# FM349ReaderV02.net
KiCad netlist of a schematic drawn in Altium Designer
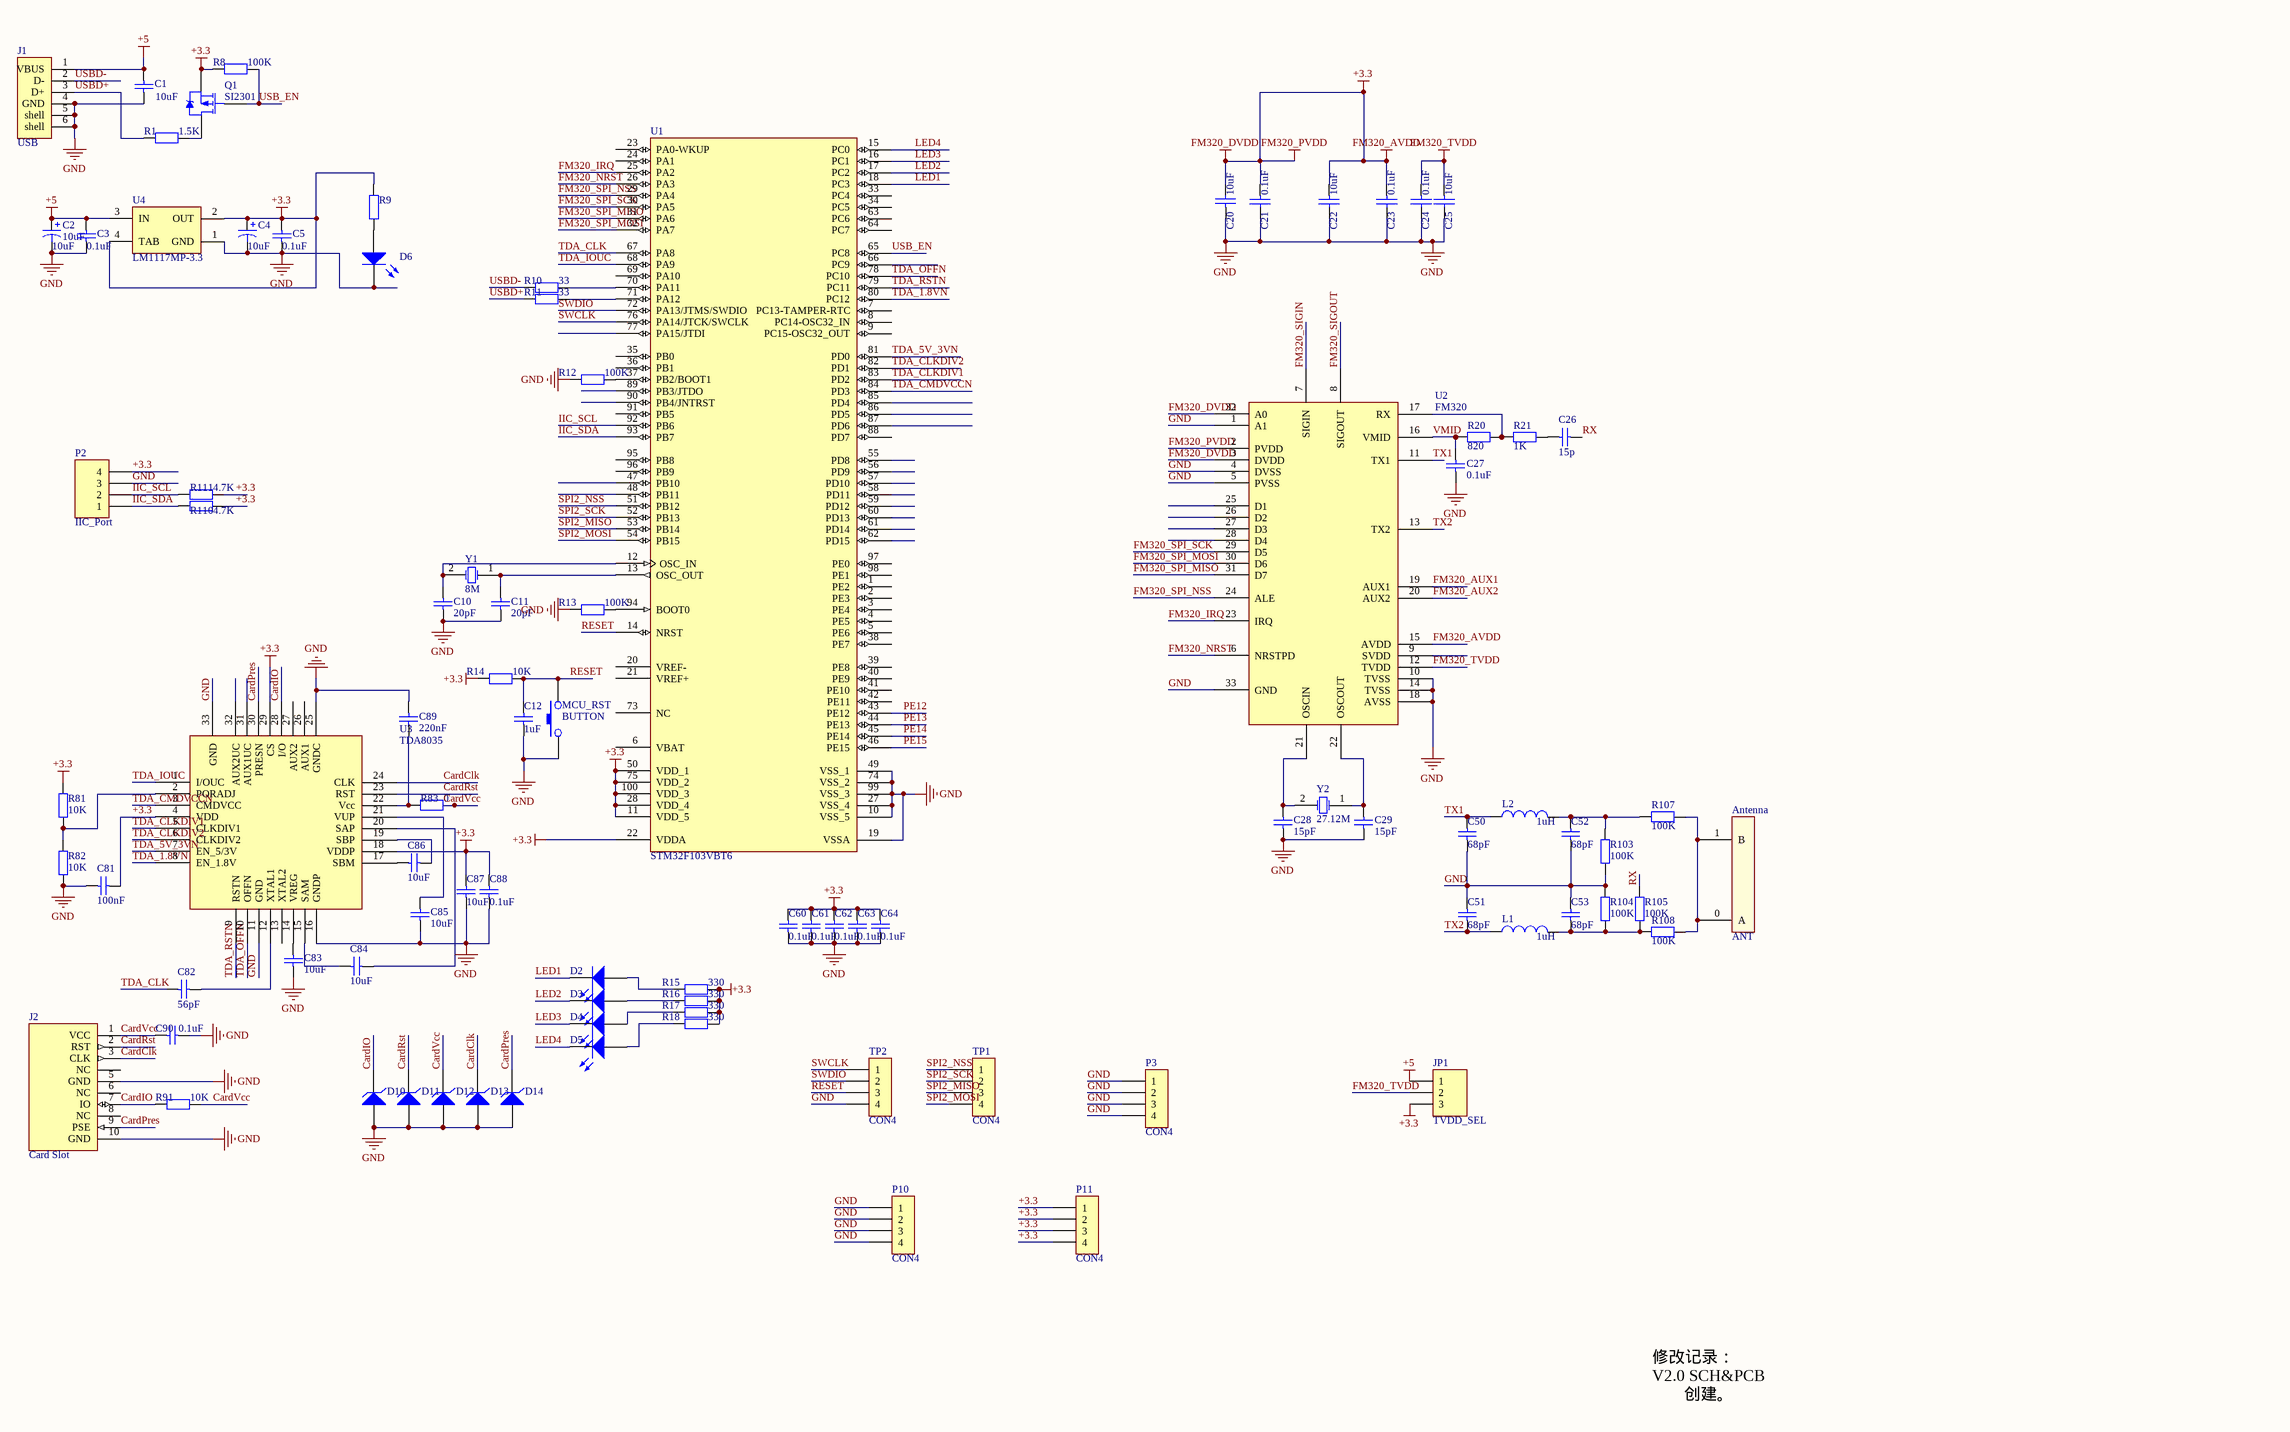
[diagram p0: FM349ReaderV02.SchDoc]

(export (version "E")
  (design (tool "Eeschema 10.0.6"))
  (components
    (comp (ref "Antenna") (value "ANT") (footprint "Antenna") (libsource (lib "FM349ReaderV01") (part "ANT")))
    (comp (ref "C1")
      (value "10uF")
      (footprint "0603")
      (description "Capacitor")
      (libsource (lib "Miscellaneous Devices") (part "Cap"))
    )
    (comp (ref "C2")
      (value "10uF")
      (footprint "0805")
      (description "Polarized Capacitor (Radial)")
      (fields (field (name "ALTIUM_VALUE") "10uF"))
      (libsource (lib "Miscellaneous Devices") (part "Cap Pol1"))
    )
    (comp (ref "C3")
      (value "0.1uF")
      (footprint "0603")
      (description "Capacitor")
      (libsource (lib "Miscellaneous Devices") (part "Cap"))
    )
    (comp (ref "C4")
      (value "10uF")
      (footprint "0805")
      (description "Polarized Capacitor (Radial)")
      (libsource (lib "Miscellaneous Devices") (part "Cap Pol1"))
    )
    (comp (ref "C5")
      (value "0.1uF")
      (footprint "0603")
      (description "Capacitor")
      (libsource (lib "Miscellaneous Devices") (part "Cap"))
    )
    (comp (ref "C10")
      (value "20pF")
      (footprint "0603")
      (description "Capacitor")
      (libsource (lib "Miscellaneous Devices") (part "Cap"))
    )
    (comp (ref "C11")
      (value "20pF")
      (footprint "0603")
      (description "Capacitor")
      (libsource (lib "Miscellaneous Devices") (part "Cap"))
    )
    (comp (ref "C12")
      (value "1uF")
      (footprint "0603")
      (description "Capacitor")
      (libsource (lib "Miscellaneous Devices") (part "Cap"))
    )
    (comp (ref "C20")
      (value "10uF")
      (footprint "0603")
      (description "Capacitor")
      (libsource (lib "SCH_LIB") (part "CAP"))
    )
    (comp (ref "C21")
      (value "0.1uF")
      (footprint "0603")
      (description "Capacitor")
      (libsource (lib "SCH_LIB") (part "CAP"))
    )
    (comp (ref "C22")
      (value "10uF")
      (footprint "0603")
      (description "Capacitor")
      (libsource (lib "SCH_LIB") (part "CAP"))
    )
    (comp (ref "C23")
      (value "0.1uF")
      (footprint "0603")
      (description "Capacitor")
      (libsource (lib "SCH_LIB") (part "CAP"))
    )
    (comp (ref "C24")
      (value "0.1uF")
      (footprint "0603")
      (description "Capacitor")
      (libsource (lib "SCH_LIB") (part "CAP"))
    )
    (comp (ref "C25")
      (value "10uF")
      (footprint "0603")
      (description "Capacitor")
      (libsource (lib "SCH_LIB") (part "CAP"))
    )
    (comp (ref "C26")
      (value "15p")
      (footprint "0603")
      (description "Capacitor")
      (fields (field (name "Comment") "0.1uF"))
      (libsource (lib "Miscellaneous Devices") (part "Cap"))
    )
    (comp (ref "C27")
      (value "0.1uF")
      (footprint "0603")
      (description "Capacitor")
      (libsource (lib "Miscellaneous Devices") (part "Cap"))
    )
    (comp (ref "C28")
      (value "15pF")
      (footprint "0603")
      (description "Capacitor")
      (libsource (lib "Miscellaneous Devices") (part "Cap"))
    )
    (comp (ref "C29")
      (value "15pF")
      (footprint "0603")
      (description "Capacitor")
      (libsource (lib "Miscellaneous Devices") (part "Cap"))
    )
    (comp (ref "C50")
      (value "68pF")
      (footprint "0603")
      (description "Capacitor")
      (libsource (lib "Miscellaneous Devices") (part "Cap"))
    )
    (comp (ref "C51")
      (value "68pF")
      (footprint "0603")
      (description "Capacitor")
      (libsource (lib "Miscellaneous Devices") (part "Cap"))
    )
    (comp (ref "C52")
      (value "68pF")
      (footprint "0603")
      (description "Capacitor")
      (libsource (lib "Miscellaneous Devices") (part "Cap"))
    )
    (comp (ref "C53")
      (value "68pF")
      (footprint "0603")
      (description "Capacitor")
      (libsource (lib "Miscellaneous Devices") (part "Cap"))
    )
    (comp (ref "C60")
      (value "0.1uF")
      (footprint "0603")
      (description "Capacitor")
      (libsource (lib "Miscellaneous Devices") (part "Cap"))
    )
    (comp (ref "C61")
      (value "0.1uF")
      (footprint "0603")
      (description "Capacitor")
      (libsource (lib "Miscellaneous Devices") (part "Cap"))
    )
    (comp (ref "C62")
      (value "0.1uF")
      (footprint "0603")
      (description "Capacitor")
      (libsource (lib "Miscellaneous Devices") (part "Cap"))
    )
    (comp (ref "C63")
      (value "0.1uF")
      (footprint "0603")
      (description "Capacitor")
      (libsource (lib "Miscellaneous Devices") (part "Cap"))
    )
    (comp (ref "C64")
      (value "0.1uF")
      (footprint "0603")
      (description "Capacitor")
      (libsource (lib "Miscellaneous Devices") (part "Cap"))
    )
    (comp (ref "C81")
      (value "100nF")
      (footprint "0603")
      (description "Capacitor")
      (fields (field (name "Comment") "0.1uF"))
      (libsource (lib "Miscellaneous Devices") (part "Cap"))
    )
    (comp (ref "C82")
      (value "56pF")
      (footprint "0603")
      (description "Capacitor")
      (fields (field (name "Comment") "0.1uF"))
      (libsource (lib "Miscellaneous Devices") (part "Cap"))
    )
    (comp (ref "C83")
      (value "10uF")
      (footprint "0603")
      (description "Capacitor")
      (fields (field (name "Comment") "0.1uF"))
      (libsource (lib "Miscellaneous Devices") (part "Cap"))
    )
    (comp (ref "C84")
      (value "10uF")
      (footprint "0603")
      (description "Capacitor")
      (fields (field (name "Comment") "0.1uF"))
      (libsource (lib "Miscellaneous Devices") (part "Cap"))
    )
    (comp (ref "C85")
      (value "10uF")
      (footprint "0603")
      (description "Capacitor")
      (fields (field (name "Comment") "0.1uF"))
      (libsource (lib "Miscellaneous Devices") (part "Cap"))
    )
    (comp (ref "C86")
      (value "10uF")
      (footprint "0603")
      (description "Capacitor")
      (fields (field (name "Comment") "0.1uF"))
      (libsource (lib "Miscellaneous Devices") (part "Cap"))
    )
    (comp (ref "C87")
      (value "10uF")
      (footprint "0603")
      (description "Capacitor")
      (fields (field (name "Comment") "0.1uF"))
      (libsource (lib "Miscellaneous Devices") (part "Cap"))
    )
    (comp (ref "C88")
      (value "0.1uF")
      (footprint "0603")
      (description "Capacitor")
      (libsource (lib "Miscellaneous Devices") (part "Cap"))
    )
    (comp (ref "C89")
      (value "220nF")
      (footprint "0603")
      (description "Capacitor")
      (fields (field (name "Comment") "0.1uF"))
      (libsource (lib "Miscellaneous Devices") (part "Cap"))
    )
    (comp (ref "C90")
      (value "0.1uF")
      (footprint "0603")
      (description "Capacitor")
      (libsource (lib "Miscellaneous Devices") (part "Cap"))
    )
    (comp (ref "D2")
      (value "LED2")
      (footprint "3.2X1.6X1.1")
      (description "Typical RED, GREEN, YELLOW, AMBER GaAs LED")
      (libsource (lib "Miscellaneous Devices") (part "LED2"))
    )
    (comp (ref "D3")
      (value "LED2")
      (footprint "3.2X1.6X1.1")
      (description "Typical RED, GREEN, YELLOW, AMBER GaAs LED")
      (libsource (lib "Miscellaneous Devices") (part "LED2"))
    )
    (comp (ref "D4")
      (value "LED2")
      (footprint "3.2X1.6X1.1")
      (description "Typical RED, GREEN, YELLOW, AMBER GaAs LED")
      (libsource (lib "Miscellaneous Devices") (part "LED2"))
    )
    (comp (ref "D5")
      (value "LED2")
      (footprint "3.2X1.6X1.1")
      (description "Typical RED, GREEN, YELLOW, AMBER GaAs LED")
      (libsource (lib "Miscellaneous Devices") (part "LED2"))
    )
    (comp (ref "D6")
      (value "LED2")
      (footprint "3.2X1.6X1.1")
      (description "Typical RED, GREEN, YELLOW, AMBER GaAs LED")
      (libsource (lib "Miscellaneous Devices") (part "LED2"))
    )
    (comp (ref "D10")
      (value "ESD")
      (footprint "SOD-323")
      (description "Zener Diode")
      (libsource (lib "Miscellaneous Devices") (part "D Zener"))
    )
    (comp (ref "D11")
      (value "ESD")
      (footprint "SOD-323")
      (description "Zener Diode")
      (libsource (lib "Miscellaneous Devices") (part "D Zener"))
    )
    (comp (ref "D12")
      (value "ESD")
      (footprint "SOD-323")
      (description "Zener Diode")
      (libsource (lib "Miscellaneous Devices") (part "D Zener"))
    )
    (comp (ref "D13")
      (value "ESD")
      (footprint "SOD-323")
      (description "Zener Diode")
      (libsource (lib "Miscellaneous Devices") (part "D Zener"))
    )
    (comp (ref "D14")
      (value "ESD")
      (footprint "SOD-323")
      (description "Zener Diode")
      (libsource (lib "Miscellaneous Devices") (part "D Zener"))
    )
    (comp (ref "J1") (value "USB") (footprint "USB-B") (libsource (lib "USB") (part "USB")))
    (comp (ref "J2")
      (value "Card Slot")
      (footprint "BIG-CARD-SLOT")
      (libsource (lib "fm274") (part "Card Slot"))
    )
    (comp (ref "JP1")
      (value "TVDD_SEL")
      (footprint "HDR1X3")
      (description "Header, 3-Pin")
      (libsource (lib "Miscellaneous Connectors") (part "Header 3"))
    )
    (comp (ref "L1")
      (value "1uH")
      (footprint "1812")
      (description "Inductor")
      (libsource (lib "Miscellaneous Devices") (part "Inductor"))
    )
    (comp (ref "L2")
      (value "1uH")
      (footprint "1812")
      (description "Inductor")
      (libsource (lib "Miscellaneous Devices") (part "Inductor"))
    )
    (comp (ref "MCU_RST")
      (value "BUTTON")
      (footprint "BUTTON-S")
      (description "乒乓球按键（压下后接通，松开自动断开），较大按键尺寸12mmX12mm选用BUTTON-L封装，较小尺寸6mmX6mm选用BUTTON-S封装")
      (libsource (lib "fm274") (part "BUTTON"))
    )
    (comp (ref "P2")
      (value "IIC_Port")
      (footprint "HDR1X4")
      (description "Header, 4-Pin")
      (libsource (lib "Miscellaneous Connectors") (part "Header 4"))
    )
    (comp (ref "P3")
      (value "CON4")
      (footprint "HDR1X4")
      (description "Connector")
      (libsource (lib "YPF") (part "CON4"))
    )
    (comp (ref "P10")
      (value "CON4")
      (footprint "HDR1X4")
      (description "Connector")
      (libsource (lib "YPF") (part "CON4"))
    )
    (comp (ref "P11")
      (value "CON4")
      (footprint "HDR1X4")
      (description "Connector")
      (libsource (lib "YPF") (part "CON4"))
    )
    (comp (ref "Q1")
      (value "SI2301")
      (footprint "SOT-23-2301")
      (description "P-Channel Power MOSFET")
      (libsource (lib "Miscellaneous Devices") (part "PMOS-2"))
    )
    (comp (ref "R1")
      (value "1.5K")
      (footprint "0603")
      (description "Resistor")
      (libsource (lib "") (part "Res2_1"))
    )
    (comp (ref "R8")
      (value "100K")
      (footprint "0603")
      (description "Resistor")
      (fields (field (name "Comment") "10K"))
      (libsource (lib "") (part "Res2_1"))
    )
    (comp (ref "R9")
      (value "1.5K")
      (footprint "0603")
      (description "Resistor")
      (libsource (lib "Miscellaneous Devices") (part "Res2"))
    )
    (comp (ref "R10")
      (value "33")
      (footprint "0603")
      (description "Resistor")
      (libsource (lib "") (part "Res2_1"))
    )
    (comp (ref "R11")
      (value "33")
      (footprint "0603")
      (description "Resistor")
      (libsource (lib "") (part "Res2_1"))
    )
    (comp (ref "R12")
      (value "100K")
      (footprint "0603")
      (description "Resistor")
      (libsource (lib "") (part "Res2_1"))
    )
    (comp (ref "R13")
      (value "100K")
      (footprint "0603")
      (description "Resistor")
      (libsource (lib "") (part "Res2_1"))
    )
    (comp (ref "R14")
      (value "10K")
      (footprint "0603")
      (description "Resistor")
      (libsource (lib "") (part "Res2_1"))
    )
    (comp (ref "R15")
      (value "330")
      (footprint "0603")
      (description "Resistor")
      (libsource (lib "") (part "Res2_1"))
    )
    (comp (ref "R16")
      (value "330")
      (footprint "0603")
      (description "Resistor")
      (libsource (lib "") (part "Res2_2"))
    )
    (comp (ref "R17")
      (value "330")
      (footprint "0603")
      (description "Resistor")
      (libsource (lib "") (part "Res2_1"))
    )
    (comp (ref "R18")
      (value "330")
      (footprint "0603")
      (description "Resistor")
      (libsource (lib "") (part "Res2_1"))
    )
    (comp (ref "R20")
      (value "820")
      (footprint "0603")
      (description "Resistor")
      (libsource (lib "") (part "Res2_2"))
    )
    (comp (ref "R21")
      (value "1K")
      (footprint "0603")
      (description "Resistor")
      (libsource (lib "") (part "Res2_2"))
    )
    (comp (ref "R81")
      (value "10K")
      (footprint "0603")
      (description "Resistor")
      (fields (field (name "Comment") "1.5K"))
      (libsource (lib "Miscellaneous Devices") (part "Res2"))
    )
    (comp (ref "R82")
      (value "10K")
      (footprint "0603")
      (description "Resistor")
      (fields (field (name "Comment") "1.5K"))
      (libsource (lib "Miscellaneous Devices") (part "Res2"))
    )
    (comp (ref "R83")
      (value "0")
      (footprint "0603")
      (description "Resistor")
      (fields (field (name "Comment") "10K"))
      (libsource (lib "") (part "Res2_1"))
    )
    (comp (ref "R91")
      (value "10K")
      (footprint "0603")
      (description "Resistor")
      (fields (field (name "Comment") "1.5K"))
      (libsource (lib "") (part "Res2_1"))
    )
    (comp (ref "R103")
      (value "100K")
      (footprint "0603")
      (description "Resistor")
      (libsource (lib "Miscellaneous Devices") (part "Res2"))
    )
    (comp (ref "R104")
      (value "100K")
      (footprint "0603")
      (description "Resistor")
      (libsource (lib "Miscellaneous Devices") (part "Res2"))
    )
    (comp (ref "R105")
      (value "100K")
      (footprint "0603")
      (description "Resistor")
      (libsource (lib "Miscellaneous Devices") (part "Res2"))
    )
    (comp (ref "R107")
      (value "100K")
      (footprint "0603")
      (description "Resistor")
      (libsource (lib "") (part "Res2_2"))
    )
    (comp (ref "R108")
      (value "100K")
      (footprint "0603")
      (description "Resistor")
      (libsource (lib "") (part "Res2_2"))
    )
    (comp (ref "R110")
      (value "4.7K")
      (footprint "0603")
      (description "Resistor")
      (fields (field (name "Comment") "1.5K"))
      (libsource (lib "") (part "Res2_2"))
    )
    (comp (ref "R111")
      (value "4.7K")
      (footprint "0603")
      (description "Resistor")
      (fields (field (name "Comment") "1.5K"))
      (libsource (lib "") (part "Res2_2"))
    )
    (comp (ref "TP1")
      (value "CON4")
      (footprint "HDR1X4")
      (description "Connector")
      (libsource (lib "YPF") (part "CON4"))
    )
    (comp (ref "TP2")
      (value "CON4")
      (footprint "HDR1X4")
      (description "Connector")
      (libsource (lib "YPF") (part "CON4"))
    )
    (comp (ref "U1")
      (value "STM32F103VBT6")
      (footprint "LQFP100_L")
      (description "STM32 ARM-based 32-bit MCU with 64 Kbytes Flash, 100-pin LQFP, Industrial Temperature")
      (libsource (lib "ST Microcontroller 32-Bit STM32") (part "STM32F103VBT6"))
    )
    (comp (ref "U2")
      (value "FM320")
      (footprint "FM320_PIN32")
      (libsource (lib "FM349ReaderV01") (part "PN5120A0HN1"))
    )
    (comp (ref "U3")
      (value "TDA8035")
      (footprint "TDA8035_PIN32")
      (libsource (lib "FM349ReaderV01") (part "TDA8035"))
    )
    (comp (ref "U4")
      (value "LM1117MP-3.3")
      (footprint "MP04A_L")
      (description "800mA Low-Dropout Linear Regulator")
      (fields
        (field (name "MANUFACTURER") "National Semiconductor")
        (field (name "DIGIKEYPARTNUMBER") "LM1117MP-3.3CT-ND")
      )
      (libsource (lib "NSC LDO") (part "LM1117MP-3.3"))
    )
    (comp (ref "Y1")
      (value "8M")
      (footprint "XTAL-0.2")
      (description "Crystal Oscillator")
      (libsource (lib "Miscellaneous Devices") (part "XTAL"))
    )
    (comp (ref "Y2")
      (value "27.12M")
      (footprint "XTAL-0.2")
      (description "Crystal Oscillator")
      (libsource (lib "Miscellaneous Devices") (part "XTAL"))
    )
  )
  (nets
    (net (code "1") (name "+3.3") (class "Default")
      (node (ref "C20") (pin "2") (pinfunction "2_2") (pintype "passive"))
      (node (ref "C21") (pin "1") (pinfunction "1_1") (pintype "passive"))
      (node (ref "C22") (pin "1") (pinfunction "1_1") (pintype "passive"))
      (node (ref "C23") (pin "1") (pinfunction "1_1") (pintype "passive"))
      (node (ref "C4") (pin "1") (pinfunction "1_1") (pintype "passive"))
      (node (ref "C5") (pin "2") (pinfunction "2_2") (pintype "passive"))
      (node (ref "C60") (pin "2") (pinfunction "2_2") (pintype "passive"))
      (node (ref "C61") (pin "2") (pinfunction "2_2") (pintype "passive"))
      (node (ref "C62") (pin "2") (pinfunction "2_2") (pintype "passive"))
      (node (ref "C63") (pin "2") (pinfunction "2_2") (pintype "passive"))
      (node (ref "C64") (pin "2") (pinfunction "2_2") (pintype "passive"))
      (node (ref "C81") (pin "1") (pinfunction "1_1") (pintype "passive"))
      (node (ref "C87") (pin "2") (pinfunction "2_2") (pintype "passive"))
      (node (ref "C88") (pin "2") (pinfunction "2_2") (pintype "passive"))
      (node (ref "JP1") (pin "3") (pinfunction "3_3") (pintype "passive"))
      (node (ref "P11") (pin "1") (pinfunction "1_1") (pintype "passive"))
      (node (ref "P11") (pin "2") (pinfunction "2_2") (pintype "passive"))
      (node (ref "P11") (pin "3") (pinfunction "3_3") (pintype "passive"))
      (node (ref "P11") (pin "4") (pinfunction "4_4") (pintype "passive"))
      (node (ref "P2") (pin "4") (pinfunction "4_4") (pintype "passive"))
      (node (ref "Q1") (pin "3") (pinfunction "S_3") (pintype "passive"))
      (node (ref "R110") (pin "1") (pinfunction "1_1") (pintype "passive"))
      (node (ref "R111") (pin "1") (pinfunction "1_1") (pintype "passive"))
      (node (ref "R14") (pin "1") (pinfunction "1_1") (pintype "passive"))
      (node (ref "R15") (pin "2") (pinfunction "2_2") (pintype "passive"))
      (node (ref "R16") (pin "1") (pinfunction "1_1") (pintype "passive"))
      (node (ref "R17") (pin "2") (pinfunction "2_2") (pintype "passive"))
      (node (ref "R18") (pin "2") (pinfunction "2_2") (pintype "passive"))
      (node (ref "R8") (pin "1") (pinfunction "1_1") (pintype "passive"))
      (node (ref "R81") (pin "2") (pinfunction "2_2") (pintype "passive"))
      (node (ref "R9") (pin "2") (pinfunction "2_2") (pintype "passive"))
      (node (ref "U1") (pin "100") (pinfunction "VDD_3_100") (pintype "power_in"))
      (node (ref "U1") (pin "11") (pinfunction "VDD_5_11") (pintype "power_in"))
      (node (ref "U1") (pin "22") (pinfunction "VDDA_22") (pintype "power_in"))
      (node (ref "U1") (pin "28") (pinfunction "VDD_4_28") (pintype "power_in"))
      (node (ref "U1") (pin "50") (pinfunction "VDD_1_50") (pintype "power_in"))
      (node (ref "U1") (pin "75") (pinfunction "VDD_2_75") (pintype "power_in"))
      (node (ref "U2") (pin "15") (pinfunction "AVDD_15") (pintype "passive"))
      (node (ref "U2") (pin "2") (pinfunction "PVDD_2") (pintype "passive"))
      (node (ref "U2") (pin "3") (pinfunction "DVDD_3") (pintype "passive"))
      (node (ref "U2") (pin "32") (pinfunction "A0_32") (pintype "passive"))
      (node (ref "U3") (pin "18") (pinfunction "VDDP_18") (pintype "passive"))
      (node (ref "U3") (pin "29") (pinfunction "CS_29") (pintype "passive"))
      (node (ref "U3") (pin "4") (pinfunction "VDD_4") (pintype "passive"))
      (node (ref "U4") (pin "2") (pinfunction "OUT_2") (pintype "power_in"))
      (node (ref "U4") (pin "4") (pinfunction "TAB_4") (pintype "power_in"))
    )
    (net (code "2") (name "+5") (class "Default")
      (node (ref "C1") (pin "2") (pinfunction "2_2") (pintype "passive"))
      (node (ref "C2") (pin "1") (pinfunction "1_1") (pintype "passive"))
      (node (ref "C3") (pin "2") (pinfunction "2_2") (pintype "passive"))
      (node (ref "J1") (pin "1") (pinfunction "VBUS_1") (pintype "passive"))
      (node (ref "JP1") (pin "1") (pinfunction "1_1") (pintype "passive"))
      (node (ref "U4") (pin "3") (pinfunction "IN_3") (pintype "power_in"))
    )
    (net (code "3") (name "/CardClk") (class "Default")
      (node (ref "D13") (pin "2") (pinfunction "K_2") (pintype "passive"))
      (node (ref "J2") (pin "3") (pinfunction "CLK_3") (pintype "output"))
      (node (ref "U3") (pin "24") (pinfunction "CLK_24") (pintype "passive"))
    )
    (net (code "4") (name "/CardIO") (class "Default")
      (node (ref "D10") (pin "2") (pinfunction "K_2") (pintype "passive"))
      (node (ref "J2") (pin "7") (pinfunction "IO_7") (pintype "bidirectional"))
      (node (ref "R91") (pin "1") (pinfunction "1_1") (pintype "passive"))
      (node (ref "U3") (pin "28") (pinfunction "I/O_28") (pintype "passive"))
    )
    (net (code "5") (name "/CardPres") (class "Default")
      (node (ref "D14") (pin "2") (pinfunction "K_2") (pintype "passive"))
      (node (ref "J2") (pin "9") (pinfunction "PSE_9") (pintype "input"))
      (node (ref "U3") (pin "30") (pinfunction "PRESN_30") (pintype "passive"))
    )
    (net (code "6") (name "/CardRst") (class "Default")
      (node (ref "D11") (pin "2") (pinfunction "K_2") (pintype "passive"))
      (node (ref "J2") (pin "2") (pinfunction "RST_2") (pintype "output"))
      (node (ref "U3") (pin "23") (pinfunction "RST_23") (pintype "passive"))
    )
    (net (code "7") (name "/CardVcc") (class "Default")
      (node (ref "C90") (pin "1") (pinfunction "1_1") (pintype "passive"))
      (node (ref "D12") (pin "2") (pinfunction "K_2") (pintype "passive"))
      (node (ref "J2") (pin "1") (pinfunction "VCC_1") (pintype "power_in"))
      (node (ref "R83") (pin "2") (pinfunction "2_2") (pintype "passive"))
      (node (ref "R91") (pin "2") (pinfunction "2_2") (pintype "passive"))
    )
    (net (code "8") (name "/FM320_AUX1") (class "Default")
      (node (ref "U2") (pin "19") (pinfunction "AUX1_19") (pintype "passive"))
    )
    (net (code "9") (name "/FM320_AUX2") (class "Default")
      (node (ref "U2") (pin "20") (pinfunction "AUX2_20") (pintype "passive"))
    )
    (net (code "10") (name "/FM320_IRQ") (class "Default")
      (node (ref "U1") (pin "25") (pinfunction "PA2_25") (pintype "bidirectional"))
      (node (ref "U2") (pin "23") (pinfunction "IRQ_23") (pintype "passive"))
    )
    (net (code "11") (name "/FM320_NRST") (class "Default")
      (node (ref "U1") (pin "26") (pinfunction "PA3_26") (pintype "bidirectional"))
      (node (ref "U2") (pin "6") (pinfunction "NRSTPD_6") (pintype "passive"))
    )
    (net (code "12") (name "/FM320_SIGIN") (class "Default")
      (node (ref "U2") (pin "7") (pinfunction "SIGIN_7") (pintype "passive"))
    )
    (net (code "13") (name "/FM320_SIGOUT") (class "Default")
      (node (ref "U2") (pin "8") (pinfunction "SIGOUT_8") (pintype "passive"))
    )
    (net (code "14") (name "/FM320_SPI_MISO") (class "Default")
      (node (ref "U1") (pin "31") (pinfunction "PA6_31") (pintype "bidirectional"))
      (node (ref "U2") (pin "31") (pinfunction "D7_31") (pintype "passive"))
    )
    (net (code "15") (name "/FM320_SPI_MOSI") (class "Default")
      (node (ref "U1") (pin "32") (pinfunction "PA7_32") (pintype "bidirectional"))
      (node (ref "U2") (pin "30") (pinfunction "D6_30") (pintype "passive"))
    )
    (net (code "16") (name "/FM320_SPI_NSS") (class "Default")
      (node (ref "U1") (pin "29") (pinfunction "PA4_29") (pintype "bidirectional"))
      (node (ref "U2") (pin "24") (pinfunction "ALE_24") (pintype "passive"))
    )
    (net (code "17") (name "/FM320_SPI_SCK") (class "Default")
      (node (ref "U1") (pin "30") (pinfunction "PA5_30") (pintype "bidirectional"))
      (node (ref "U2") (pin "29") (pinfunction "D5_29") (pintype "passive"))
    )
    (net (code "18") (name "/IIC_SCL") (class "Default")
      (node (ref "P2") (pin "2") (pinfunction "2_2") (pintype "passive"))
      (node (ref "R111") (pin "2") (pinfunction "2_2") (pintype "passive"))
      (node (ref "U1") (pin "92") (pinfunction "PB6_92") (pintype "bidirectional"))
    )
    (net (code "19") (name "/IIC_SDA") (class "Default")
      (node (ref "P2") (pin "1") (pinfunction "1_1") (pintype "passive"))
      (node (ref "R110") (pin "2") (pinfunction "2_2") (pintype "passive"))
      (node (ref "U1") (pin "93") (pinfunction "PB7_93") (pintype "bidirectional"))
    )
    (net (code "20") (name "/LED1") (class "Default")
      (node (ref "D2") (pin "2") (pinfunction "K_2") (pintype "passive"))
      (node (ref "U1") (pin "18") (pinfunction "PC3_18") (pintype "bidirectional"))
    )
    (net (code "21") (name "/LED2") (class "Default")
      (node (ref "D3") (pin "2") (pinfunction "K_2") (pintype "passive"))
      (node (ref "U1") (pin "17") (pinfunction "PC2_17") (pintype "bidirectional"))
    )
    (net (code "22") (name "/LED3") (class "Default")
      (node (ref "D4") (pin "2") (pinfunction "K_2") (pintype "passive"))
      (node (ref "U1") (pin "16") (pinfunction "PC1_16") (pintype "bidirectional"))
    )
    (net (code "23") (name "/LED4") (class "Default")
      (node (ref "D5") (pin "2") (pinfunction "K_2") (pintype "passive"))
      (node (ref "U1") (pin "15") (pinfunction "PC0_15") (pintype "bidirectional"))
    )
    (net (code "24") (name "/PE12") (class "Default")
      (node (ref "U1") (pin "43") (pinfunction "PE12_43") (pintype "bidirectional"))
    )
    (net (code "25") (name "/PE13") (class "Default")
      (node (ref "U1") (pin "44") (pinfunction "PE13_44") (pintype "bidirectional"))
    )
    (net (code "26") (name "/PE14") (class "Default")
      (node (ref "U1") (pin "45") (pinfunction "PE14_45") (pintype "bidirectional"))
    )
    (net (code "27") (name "/PE15") (class "Default")
      (node (ref "U1") (pin "46") (pinfunction "PE15_46") (pintype "bidirectional"))
    )
    (net (code "28") (name "/RESET") (class "Default")
      (node (ref "C12") (pin "2") (pinfunction "2_2") (pintype "passive"))
      (node (ref "MCU_RST") (pin "2") (pinfunction "2_2") (pintype "passive"))
      (node (ref "R14") (pin "2") (pinfunction "2_2") (pintype "passive"))
      (node (ref "TP2") (pin "3") (pinfunction "3_3") (pintype "passive"))
      (node (ref "U1") (pin "14") (pinfunction "NRST_14") (pintype "bidirectional"))
    )
    (net (code "29") (name "/RX") (class "Default")
      (node (ref "C26") (pin "1") (pinfunction "1_1") (pintype "passive"))
      (node (ref "R105") (pin "2") (pinfunction "2_2") (pintype "passive"))
    )
    (net (code "30") (name "/SPI2_MISO") (class "Default")
      (node (ref "TP1") (pin "3") (pinfunction "3_3") (pintype "passive"))
      (node (ref "U1") (pin "53") (pinfunction "PB14_53") (pintype "bidirectional"))
    )
    (net (code "31") (name "/SPI2_MOSI") (class "Default")
      (node (ref "TP1") (pin "4") (pinfunction "4_4") (pintype "passive"))
      (node (ref "U1") (pin "54") (pinfunction "PB15_54") (pintype "bidirectional"))
    )
    (net (code "32") (name "/SPI2_NSS") (class "Default")
      (node (ref "TP1") (pin "1") (pinfunction "1_1") (pintype "passive"))
      (node (ref "U1") (pin "51") (pinfunction "PB12_51") (pintype "bidirectional"))
    )
    (net (code "33") (name "/SPI2_SCK") (class "Default")
      (node (ref "TP1") (pin "2") (pinfunction "2_2") (pintype "passive"))
      (node (ref "U1") (pin "52") (pinfunction "PB13_52") (pintype "bidirectional"))
    )
    (net (code "34") (name "/SWCLK") (class "Default")
      (node (ref "TP2") (pin "1") (pinfunction "1_1") (pintype "passive"))
      (node (ref "U1") (pin "76") (pinfunction "PA14/JTCK/SWCLK_76") (pintype "bidirectional"))
    )
    (net (code "35") (name "/SWDIO") (class "Default")
      (node (ref "TP2") (pin "2") (pinfunction "2_2") (pintype "passive"))
      (node (ref "U1") (pin "72") (pinfunction "PA13/JTMS/SWDIO_72") (pintype "bidirectional"))
    )
    (net (code "36") (name "/TDA_1.8VN") (class "Default")
      (node (ref "U1") (pin "80") (pinfunction "PC12_80") (pintype "bidirectional"))
      (node (ref "U3") (pin "8") (pinfunction "EN_1.8V_8") (pintype "passive"))
    )
    (net (code "37") (name "/TDA_5V_3VN") (class "Default")
      (node (ref "U1") (pin "81") (pinfunction "PD0_81") (pintype "bidirectional"))
      (node (ref "U3") (pin "7") (pinfunction "EN_5/3V_7") (pintype "passive"))
    )
    (net (code "38") (name "/TDA_CLK") (class "Default")
      (node (ref "C82") (pin "1") (pinfunction "1_1") (pintype "passive"))
      (node (ref "U1") (pin "67") (pinfunction "PA8_67") (pintype "bidirectional"))
    )
    (net (code "39") (name "/TDA_CLKDIV1") (class "Default")
      (node (ref "U1") (pin "83") (pinfunction "PD2_83") (pintype "bidirectional"))
      (node (ref "U3") (pin "5") (pinfunction "CLKDIV1_5") (pintype "passive"))
    )
    (net (code "40") (name "/TDA_CLKDIV2") (class "Default")
      (node (ref "U1") (pin "82") (pinfunction "PD1_82") (pintype "bidirectional"))
      (node (ref "U3") (pin "6") (pinfunction "CLKDIV2_6") (pintype "passive"))
    )
    (net (code "41") (name "/TDA_CMDVCCN") (class "Default")
      (node (ref "U1") (pin "84") (pinfunction "PD3_84") (pintype "bidirectional"))
      (node (ref "U3") (pin "3") (pinfunction "CMDVCC_3") (pintype "passive"))
    )
    (net (code "42") (name "/TDA_IOUC") (class "Default")
      (node (ref "U1") (pin "68") (pinfunction "PA9_68") (pintype "bidirectional"))
      (node (ref "U3") (pin "1") (pinfunction "I/OUC_1") (pintype "passive"))
    )
    (net (code "43") (name "/TDA_OFFN") (class "Default")
      (node (ref "U1") (pin "78") (pinfunction "PC10_78") (pintype "bidirectional"))
      (node (ref "U3") (pin "10") (pinfunction "OFFN_10") (pintype "passive"))
    )
    (net (code "44") (name "/TDA_RSTN") (class "Default")
      (node (ref "U1") (pin "79") (pinfunction "PC11_79") (pintype "bidirectional"))
      (node (ref "U3") (pin "9") (pinfunction "RSTN_9") (pintype "passive"))
    )
    (net (code "45") (name "/TX1") (class "Default")
      (node (ref "C50") (pin "1") (pinfunction "1_1") (pintype "passive"))
      (node (ref "L2") (pin "1") (pinfunction "1_1") (pintype "passive"))
      (node (ref "U2") (pin "11") (pinfunction "TX1_11") (pintype "passive"))
    )
    (net (code "46") (name "/TX2") (class "Default")
      (node (ref "C51") (pin "2") (pinfunction "2_2") (pintype "passive"))
      (node (ref "L1") (pin "1") (pinfunction "1_1") (pintype "passive"))
      (node (ref "U2") (pin "13") (pinfunction "TX2_13") (pintype "passive"))
    )
    (net (code "47") (name "/USBD+") (class "Default")
      (node (ref "J1") (pin "3") (pinfunction "D+_3") (pintype "passive"))
      (node (ref "R1") (pin "1") (pinfunction "1_1") (pintype "passive"))
      (node (ref "R11") (pin "1") (pinfunction "1_1") (pintype "passive"))
    )
    (net (code "48") (name "/USBD-") (class "Default")
      (node (ref "J1") (pin "2") (pinfunction "D-_2") (pintype "passive"))
      (node (ref "R10") (pin "1") (pinfunction "1_1") (pintype "passive"))
    )
    (net (code "49") (name "/USB_EN") (class "Default")
      (node (ref "Q1") (pin "1") (pinfunction "G_1") (pintype "passive"))
      (node (ref "R8") (pin "2") (pinfunction "2_2") (pintype "passive"))
      (node (ref "U1") (pin "65") (pinfunction "PC8_65") (pintype "bidirectional"))
    )
    (net (code "50") (name "/VMID") (class "Default")
      (node (ref "C27") (pin "1") (pinfunction "1_1") (pintype "passive"))
      (node (ref "R20") (pin "2") (pinfunction "2_2") (pintype "passive"))
      (node (ref "U2") (pin "16") (pinfunction "VMID_16") (pintype "passive"))
    )
    (net (code "51") (name "FM320_TVDD") (class "Default")
      (node (ref "C24") (pin "1") (pinfunction "1_1") (pintype "passive"))
      (node (ref "C25") (pin "1") (pinfunction "1_1") (pintype "passive"))
      (node (ref "JP1") (pin "2") (pinfunction "2_2") (pintype "passive"))
      (node (ref "U2") (pin "12") (pinfunction "TVDD_12") (pintype "passive"))
    )
    (net (code "52") (name "GND") (class "Default")
      (node (ref "C1") (pin "1") (pinfunction "1_1") (pintype "passive"))
      (node (ref "C10") (pin "1") (pinfunction "1_1") (pintype "passive"))
      (node (ref "C11") (pin "1") (pinfunction "1_1") (pintype "passive"))
      (node (ref "C12") (pin "1") (pinfunction "1_1") (pintype "passive"))
      (node (ref "C2") (pin "2") (pinfunction "2_2") (pintype "passive"))
      (node (ref "C20") (pin "1") (pinfunction "1_1") (pintype "passive"))
      (node (ref "C21") (pin "2") (pinfunction "2_2") (pintype "passive"))
      (node (ref "C22") (pin "2") (pinfunction "2_2") (pintype "passive"))
      (node (ref "C23") (pin "2") (pinfunction "2_2") (pintype "passive"))
      (node (ref "C24") (pin "2") (pinfunction "2_2") (pintype "passive"))
      (node (ref "C25") (pin "2") (pinfunction "2_2") (pintype "passive"))
      (node (ref "C27") (pin "2") (pinfunction "2_2") (pintype "passive"))
      (node (ref "C28") (pin "1") (pinfunction "1_1") (pintype "passive"))
      (node (ref "C29") (pin "1") (pinfunction "1_1") (pintype "passive"))
      (node (ref "C3") (pin "1") (pinfunction "1_1") (pintype "passive"))
      (node (ref "C4") (pin "2") (pinfunction "2_2") (pintype "passive"))
      (node (ref "C5") (pin "1") (pinfunction "1_1") (pintype "passive"))
      (node (ref "C50") (pin "2") (pinfunction "2_2") (pintype "passive"))
      (node (ref "C51") (pin "1") (pinfunction "1_1") (pintype "passive"))
      (node (ref "C52") (pin "2") (pinfunction "2_2") (pintype "passive"))
      (node (ref "C53") (pin "1") (pinfunction "1_1") (pintype "passive"))
      (node (ref "C60") (pin "1") (pinfunction "1_1") (pintype "passive"))
      (node (ref "C61") (pin "1") (pinfunction "1_1") (pintype "passive"))
      (node (ref "C62") (pin "1") (pinfunction "1_1") (pintype "passive"))
      (node (ref "C63") (pin "1") (pinfunction "1_1") (pintype "passive"))
      (node (ref "C64") (pin "1") (pinfunction "1_1") (pintype "passive"))
      (node (ref "C81") (pin "2") (pinfunction "2_2") (pintype "passive"))
      (node (ref "C83") (pin "2") (pinfunction "2_2") (pintype "passive"))
      (node (ref "C85") (pin "1") (pinfunction "1_1") (pintype "passive"))
      (node (ref "C87") (pin "1") (pinfunction "1_1") (pintype "passive"))
      (node (ref "C88") (pin "1") (pinfunction "1_1") (pintype "passive"))
      (node (ref "C89") (pin "1") (pinfunction "1_1") (pintype "passive"))
      (node (ref "C90") (pin "2") (pinfunction "2_2") (pintype "passive"))
      (node (ref "D10") (pin "1") (pinfunction "A_1") (pintype "passive"))
      (node (ref "D11") (pin "1") (pinfunction "A_1") (pintype "passive"))
      (node (ref "D12") (pin "1") (pinfunction "A_1") (pintype "passive"))
      (node (ref "D13") (pin "1") (pinfunction "A_1") (pintype "passive"))
      (node (ref "D14") (pin "1") (pinfunction "A_1") (pintype "passive"))
      (node (ref "D6") (pin "2") (pinfunction "K_2") (pintype "passive"))
      (node (ref "J1") (pin "4") (pinfunction "GND_4") (pintype "passive"))
      (node (ref "J1") (pin "5") (pinfunction "shell_5") (pintype "passive"))
      (node (ref "J1") (pin "6") (pinfunction "shell_6") (pintype "passive"))
      (node (ref "J2") (pin "10") (pinfunction "GND_10") (pintype "power_in"))
      (node (ref "J2") (pin "5") (pinfunction "GND_5") (pintype "power_in"))
      (node (ref "MCU_RST") (pin "1") (pinfunction "1_1") (pintype "passive"))
      (node (ref "P10") (pin "1") (pinfunction "1_1") (pintype "passive"))
      (node (ref "P10") (pin "2") (pinfunction "2_2") (pintype "passive"))
      (node (ref "P10") (pin "3") (pinfunction "3_3") (pintype "passive"))
      (node (ref "P10") (pin "4") (pinfunction "4_4") (pintype "passive"))
      (node (ref "P2") (pin "3") (pinfunction "3_3") (pintype "passive"))
      (node (ref "P3") (pin "1") (pinfunction "1_1") (pintype "passive"))
      (node (ref "P3") (pin "2") (pinfunction "2_2") (pintype "passive"))
      (node (ref "P3") (pin "3") (pinfunction "3_3") (pintype "passive"))
      (node (ref "P3") (pin "4") (pinfunction "4_4") (pintype "passive"))
      (node (ref "R103") (pin "1") (pinfunction "1_1") (pintype "passive"))
      (node (ref "R104") (pin "2") (pinfunction "2_2") (pintype "passive"))
      (node (ref "R12") (pin "1") (pinfunction "1_1") (pintype "passive"))
      (node (ref "R13") (pin "1") (pinfunction "1_1") (pintype "passive"))
      (node (ref "R82") (pin "1") (pinfunction "1_1") (pintype "passive"))
      (node (ref "TP2") (pin "4") (pinfunction "4_4") (pintype "passive"))
      (node (ref "U1") (pin "10") (pinfunction "VSS_5_10") (pintype "power_in"))
      (node (ref "U1") (pin "19") (pinfunction "VSSA_19") (pintype "power_in"))
      (node (ref "U1") (pin "27") (pinfunction "VSS_4_27") (pintype "power_in"))
      (node (ref "U1") (pin "49") (pinfunction "VSS_1_49") (pintype "power_in"))
      (node (ref "U1") (pin "74") (pinfunction "VSS_2_74") (pintype "power_in"))
      (node (ref "U1") (pin "99") (pinfunction "VSS_3_99") (pintype "power_in"))
      (node (ref "U2") (pin "1") (pinfunction "A1_1") (pintype "passive"))
      (node (ref "U2") (pin "10") (pinfunction "TVSS_10") (pintype "passive"))
      (node (ref "U2") (pin "14") (pinfunction "TVSS_14") (pintype "passive"))
      (node (ref "U2") (pin "18") (pinfunction "AVSS_18") (pintype "passive"))
      (node (ref "U2") (pin "33") (pinfunction "GND_33") (pintype "passive"))
      (node (ref "U2") (pin "4") (pinfunction "DVSS_4") (pintype "passive"))
      (node (ref "U2") (pin "5") (pinfunction "PVSS_5") (pintype "passive"))
      (node (ref "U3") (pin "11") (pinfunction "GND_11") (pintype "passive"))
      (node (ref "U3") (pin "16") (pinfunction "GNDP_16") (pintype "passive"))
      (node (ref "U3") (pin "25") (pinfunction "GNDC_25") (pintype "passive"))
      (node (ref "U3") (pin "33") (pinfunction "GND_33") (pintype "passive"))
      (node (ref "U4") (pin "1") (pinfunction "GND_1") (pintype "power_in"))
    )
    (net (code "53") (name "Net-(Antenna-A)") (class "Default")
      (node (ref "Antenna") (pin "0") (pinfunction "A_0") (pintype "passive"))
      (node (ref "Antenna") (pin "1") (pinfunction "B_1") (pintype "passive"))
      (node (ref "R107") (pin "1") (pinfunction "1_1") (pintype "passive"))
      (node (ref "R108") (pin "1") (pinfunction "1_1") (pintype "passive"))
    )
    (net (code "54") (name "Net-(C26-Pad2)") (class "Default")
      (node (ref "C26") (pin "2") (pinfunction "2_2") (pintype "passive"))
      (node (ref "R21") (pin "1") (pinfunction "1_1") (pintype "passive"))
    )
    (net (code "55") (name "Net-(C52-Pad1)") (class "Default")
      (node (ref "C52") (pin "1") (pinfunction "1_1") (pintype "passive"))
      (node (ref "L2") (pin "2") (pinfunction "2_2") (pintype "passive"))
      (node (ref "R103") (pin "2") (pinfunction "2_2") (pintype "passive"))
      (node (ref "R107") (pin "2") (pinfunction "2_2") (pintype "passive"))
    )
    (net (code "56") (name "Net-(C53-Pad2)") (class "Default")
      (node (ref "C53") (pin "2") (pinfunction "2_2") (pintype "passive"))
      (node (ref "L1") (pin "2") (pinfunction "2_2") (pintype "passive"))
      (node (ref "R104") (pin "1") (pinfunction "1_1") (pintype "passive"))
      (node (ref "R105") (pin "1") (pinfunction "1_1") (pintype "passive"))
      (node (ref "R108") (pin "2") (pinfunction "2_2") (pintype "passive"))
    )
    (net (code "57") (name "Net-(D2-A)") (class "Default")
      (node (ref "D2") (pin "1") (pinfunction "A_1") (pintype "passive"))
      (node (ref "R15") (pin "1") (pinfunction "1_1") (pintype "passive"))
    )
    (net (code "58") (name "Net-(D3-A)") (class "Default")
      (node (ref "D3") (pin "1") (pinfunction "A_1") (pintype "passive"))
      (node (ref "R16") (pin "2") (pinfunction "2_2") (pintype "passive"))
    )
    (net (code "59") (name "Net-(D4-A)") (class "Default")
      (node (ref "D4") (pin "1") (pinfunction "A_1") (pintype "passive"))
      (node (ref "R17") (pin "1") (pinfunction "1_1") (pintype "passive"))
    )
    (net (code "60") (name "Net-(D5-A)") (class "Default")
      (node (ref "D5") (pin "1") (pinfunction "A_1") (pintype "passive"))
      (node (ref "R18") (pin "1") (pinfunction "1_1") (pintype "passive"))
    )
    (net (code "61") (name "Net-(D6-A)") (class "Default")
      (node (ref "D6") (pin "1") (pinfunction "A_1") (pintype "passive"))
      (node (ref "R9") (pin "1") (pinfunction "1_1") (pintype "passive"))
    )
    (net (code "62") (name "Net-(Q1-D)") (class "Default")
      (node (ref "Q1") (pin "2") (pinfunction "D_2") (pintype "passive"))
      (node (ref "R1") (pin "2") (pinfunction "2_2") (pintype "passive"))
    )
    (net (code "63") (name "Net-(U1-BOOT0)") (class "Default")
      (node (ref "R13") (pin "2") (pinfunction "2_2") (pintype "passive"))
      (node (ref "U1") (pin "94") (pinfunction "BOOT0_94") (pintype "input"))
    )
    (net (code "64") (name "Net-(U1-OSC_IN)") (class "Default")
      (node (ref "C10") (pin "2") (pinfunction "2_2") (pintype "passive"))
      (node (ref "U1") (pin "12") (pinfunction "OSC_IN_12") (pintype "input"))
      (node (ref "Y1") (pin "2") (pinfunction "OSC2_2") (pintype "passive"))
    )
    (net (code "65") (name "Net-(U1-OSC_OUT)") (class "Default")
      (node (ref "C11") (pin "2") (pinfunction "2_2") (pintype "passive"))
      (node (ref "U1") (pin "13") (pinfunction "OSC_OUT_13") (pintype "output"))
      (node (ref "Y1") (pin "1") (pinfunction "OSC1_1") (pintype "passive"))
    )
    (net (code "66") (name "Net-(U1-PA11)") (class "Default")
      (node (ref "R10") (pin "2") (pinfunction "2_2") (pintype "passive"))
      (node (ref "U1") (pin "70") (pinfunction "PA11_70") (pintype "bidirectional"))
    )
    (net (code "67") (name "Net-(U1-PA12)") (class "Default")
      (node (ref "R11") (pin "2") (pinfunction "2_2") (pintype "passive"))
      (node (ref "U1") (pin "71") (pinfunction "PA12_71") (pintype "bidirectional"))
    )
    (net (code "68") (name "Net-(U1-PB2{slash}BOOT1)") (class "Default")
      (node (ref "R12") (pin "2") (pinfunction "2_2") (pintype "passive"))
      (node (ref "U1") (pin "37") (pinfunction "PB2/BOOT1_37") (pintype "bidirectional"))
    )
    (net (code "69") (name "Net-(U2-OSCIN)") (class "Default")
      (node (ref "C28") (pin "2") (pinfunction "2_2") (pintype "passive"))
      (node (ref "U2") (pin "21") (pinfunction "OSCIN_21") (pintype "passive"))
      (node (ref "Y2") (pin "2") (pinfunction "OSC2_2") (pintype "passive"))
    )
    (net (code "70") (name "Net-(U2-OSCOUT)") (class "Default")
      (node (ref "C29") (pin "2") (pinfunction "2_2") (pintype "passive"))
      (node (ref "U2") (pin "22") (pinfunction "OSCOUT_22") (pintype "passive"))
      (node (ref "Y2") (pin "1") (pinfunction "OSC1_1") (pintype "passive"))
    )
    (net (code "71") (name "Net-(U2-RX)") (class "Default")
      (node (ref "R20") (pin "1") (pinfunction "1_1") (pintype "passive"))
      (node (ref "R21") (pin "2") (pinfunction "2_2") (pintype "passive"))
      (node (ref "U2") (pin "17") (pinfunction "RX_17") (pintype "passive"))
    )
    (net (code "72") (name "Net-(U3-PORADJ)") (class "Default")
      (node (ref "R81") (pin "1") (pinfunction "1_1") (pintype "passive"))
      (node (ref "R82") (pin "2") (pinfunction "2_2") (pintype "passive"))
      (node (ref "U3") (pin "2") (pinfunction "PORADJ_2") (pintype "passive"))
    )
    (net (code "73") (name "Net-(U3-SAM)") (class "Default")
      (node (ref "C84") (pin "2") (pinfunction "2_2") (pintype "passive"))
      (node (ref "U3") (pin "15") (pinfunction "SAM_15") (pintype "passive"))
    )
    (net (code "74") (name "Net-(U3-SAP)") (class "Default")
      (node (ref "C84") (pin "1") (pinfunction "1_1") (pintype "passive"))
      (node (ref "U3") (pin "20") (pinfunction "SAP_20") (pintype "passive"))
    )
    (net (code "75") (name "Net-(U3-SBM)") (class "Default")
      (node (ref "C86") (pin "2") (pinfunction "2_2") (pintype "passive"))
      (node (ref "U3") (pin "17") (pinfunction "SBM_17") (pintype "passive"))
    )
    (net (code "76") (name "Net-(U3-SBP)") (class "Default")
      (node (ref "C86") (pin "1") (pinfunction "1_1") (pintype "passive"))
      (node (ref "U3") (pin "19") (pinfunction "SBP_19") (pintype "passive"))
    )
    (net (code "77") (name "Net-(U3-VREG)") (class "Default")
      (node (ref "C83") (pin "1") (pinfunction "1_1") (pintype "passive"))
      (node (ref "U3") (pin "14") (pinfunction "VREG_14") (pintype "passive"))
    )
    (net (code "78") (name "Net-(U3-VUP)") (class "Default")
      (node (ref "C85") (pin "2") (pinfunction "2_2") (pintype "passive"))
      (node (ref "U3") (pin "21") (pinfunction "VUP_21") (pintype "passive"))
    )
    (net (code "79") (name "Net-(U3-Vcc)") (class "Default")
      (node (ref "C89") (pin "2") (pinfunction "2_2") (pintype "passive"))
      (node (ref "R83") (pin "1") (pinfunction "1_1") (pintype "passive"))
      (node (ref "U3") (pin "22") (pinfunction "Vcc_22") (pintype "passive"))
    )
    (net (code "80") (name "Net-(U3-XTAL1)") (class "Default")
      (node (ref "C82") (pin "2") (pinfunction "2_2") (pintype "passive"))
      (node (ref "U3") (pin "12") (pinfunction "XTAL1_12") (pintype "passive"))
    )
    (net (code "81") (name "unconnected-(J2-NC-Pad4)") (class "Default")
      (node (ref "J2") (pin "4") (pinfunction "NC_4") (pintype "passive"))
    )
    (net (code "82") (name "unconnected-(J2-NC-Pad6)") (class "Default")
      (node (ref "J2") (pin "6") (pinfunction "NC_6") (pintype "passive"))
    )
    (net (code "83") (name "unconnected-(J2-NC-Pad8)") (class "Default")
      (node (ref "J2") (pin "8") (pinfunction "NC_8") (pintype "passive"))
    )
    (net (code "84") (name "unconnected-(U1-NC-Pad73)") (class "Default")
      (node (ref "U1") (pin "73") (pinfunction "NC_73") (pintype "passive"))
    )
    (net (code "85") (name "unconnected-(U1-PA0-WKUP-Pad23)") (class "Default")
      (node (ref "U1") (pin "23") (pinfunction "PA0-WKUP_23") (pintype "bidirectional"))
    )
    (net (code "86") (name "unconnected-(U1-PA1-Pad24)") (class "Default")
      (node (ref "U1") (pin "24") (pinfunction "PA1_24") (pintype "bidirectional"))
    )
    (net (code "87") (name "unconnected-(U1-PA10-Pad69)") (class "Default")
      (node (ref "U1") (pin "69") (pinfunction "PA10_69") (pintype "bidirectional"))
    )
    (net (code "88") (name "unconnected-(U1-PA15{slash}JTDI-Pad77)") (class "Default")
      (node (ref "U1") (pin "77") (pinfunction "PA15/JTDI_77") (pintype "bidirectional"))
    )
    (net (code "89") (name "unconnected-(U1-PB0-Pad35)") (class "Default")
      (node (ref "U1") (pin "35") (pinfunction "PB0_35") (pintype "bidirectional"))
    )
    (net (code "90") (name "unconnected-(U1-PB1-Pad36)") (class "Default")
      (node (ref "U1") (pin "36") (pinfunction "PB1_36") (pintype "bidirectional"))
    )
    (net (code "91") (name "unconnected-(U1-PB3{slash}JTDO-Pad89)") (class "Default")
      (node (ref "U1") (pin "89") (pinfunction "PB3/JTDO_89") (pintype "bidirectional"))
    )
    (net (code "92") (name "unconnected-(U1-PB4{slash}JNTRST-Pad90)") (class "Default")
      (node (ref "U1") (pin "90") (pinfunction "PB4/JNTRST_90") (pintype "bidirectional"))
    )
    (net (code "93") (name "unconnected-(U1-PB5-Pad91)") (class "Default")
      (node (ref "U1") (pin "91") (pinfunction "PB5_91") (pintype "bidirectional"))
    )
    (net (code "94") (name "unconnected-(U1-PB8-Pad95)") (class "Default")
      (node (ref "U1") (pin "95") (pinfunction "PB8_95") (pintype "bidirectional"))
    )
    (net (code "95") (name "unconnected-(U1-PB9-Pad96)") (class "Default")
      (node (ref "U1") (pin "96") (pinfunction "PB9_96") (pintype "bidirectional"))
    )
    (net (code "96") (name "unconnected-(U1-PB10-Pad47)") (class "Default")
      (node (ref "U1") (pin "47") (pinfunction "PB10_47") (pintype "bidirectional"))
    )
    (net (code "97") (name "unconnected-(U1-PB11-Pad48)") (class "Default")
      (node (ref "U1") (pin "48") (pinfunction "PB11_48") (pintype "bidirectional"))
    )
    (net (code "98") (name "unconnected-(U1-PC4-Pad33)") (class "Default")
      (node (ref "U1") (pin "33") (pinfunction "PC4_33") (pintype "bidirectional"))
    )
    (net (code "99") (name "unconnected-(U1-PC5-Pad34)") (class "Default")
      (node (ref "U1") (pin "34") (pinfunction "PC5_34") (pintype "bidirectional"))
    )
    (net (code "100") (name "unconnected-(U1-PC6-Pad63)") (class "Default")
      (node (ref "U1") (pin "63") (pinfunction "PC6_63") (pintype "bidirectional"))
    )
    (net (code "101") (name "unconnected-(U1-PC7-Pad64)") (class "Default")
      (node (ref "U1") (pin "64") (pinfunction "PC7_64") (pintype "bidirectional"))
    )
    (net (code "102") (name "unconnected-(U1-PC9-Pad66)") (class "Default")
      (node (ref "U1") (pin "66") (pinfunction "PC9_66") (pintype "bidirectional"))
    )
    (net (code "103") (name "unconnected-(U1-PC13-TAMPER-RTC-Pad7)") (class "Default")
      (node (ref "U1") (pin "7") (pinfunction "PC13-TAMPER-RTC_7") (pintype "bidirectional"))
    )
    (net (code "104") (name "unconnected-(U1-PC14-OSC32_IN-Pad8)") (class "Default")
      (node (ref "U1") (pin "8") (pinfunction "PC14-OSC32_IN_8") (pintype "bidirectional"))
    )
    (net (code "105") (name "unconnected-(U1-PC15-OSC32_OUT-Pad9)") (class "Default")
      (node (ref "U1") (pin "9") (pinfunction "PC15-OSC32_OUT_9") (pintype "bidirectional"))
    )
    (net (code "106") (name "unconnected-(U1-PD4-Pad85)") (class "Default")
      (node (ref "U1") (pin "85") (pinfunction "PD4_85") (pintype "bidirectional"))
    )
    (net (code "107") (name "unconnected-(U1-PD5-Pad86)") (class "Default")
      (node (ref "U1") (pin "86") (pinfunction "PD5_86") (pintype "bidirectional"))
    )
    (net (code "108") (name "unconnected-(U1-PD6-Pad87)") (class "Default")
      (node (ref "U1") (pin "87") (pinfunction "PD6_87") (pintype "bidirectional"))
    )
    (net (code "109") (name "unconnected-(U1-PD7-Pad88)") (class "Default")
      (node (ref "U1") (pin "88") (pinfunction "PD7_88") (pintype "bidirectional"))
    )
    (net (code "110") (name "unconnected-(U1-PD8-Pad55)") (class "Default")
      (node (ref "U1") (pin "55") (pinfunction "PD8_55") (pintype "bidirectional"))
    )
    (net (code "111") (name "unconnected-(U1-PD9-Pad56)") (class "Default")
      (node (ref "U1") (pin "56") (pinfunction "PD9_56") (pintype "bidirectional"))
    )
    (net (code "112") (name "unconnected-(U1-PD10-Pad57)") (class "Default")
      (node (ref "U1") (pin "57") (pinfunction "PD10_57") (pintype "bidirectional"))
    )
    (net (code "113") (name "unconnected-(U1-PD11-Pad58)") (class "Default")
      (node (ref "U1") (pin "58") (pinfunction "PD11_58") (pintype "bidirectional"))
    )
    (net (code "114") (name "unconnected-(U1-PD12-Pad59)") (class "Default")
      (node (ref "U1") (pin "59") (pinfunction "PD12_59") (pintype "bidirectional"))
    )
    (net (code "115") (name "unconnected-(U1-PD13-Pad60)") (class "Default")
      (node (ref "U1") (pin "60") (pinfunction "PD13_60") (pintype "bidirectional"))
    )
    (net (code "116") (name "unconnected-(U1-PD14-Pad61)") (class "Default")
      (node (ref "U1") (pin "61") (pinfunction "PD14_61") (pintype "bidirectional"))
    )
    (net (code "117") (name "unconnected-(U1-PD15-Pad62)") (class "Default")
      (node (ref "U1") (pin "62") (pinfunction "PD15_62") (pintype "bidirectional"))
    )
    (net (code "118") (name "unconnected-(U1-PE0-Pad97)") (class "Default")
      (node (ref "U1") (pin "97") (pinfunction "PE0_97") (pintype "bidirectional"))
    )
    (net (code "119") (name "unconnected-(U1-PE1-Pad98)") (class "Default")
      (node (ref "U1") (pin "98") (pinfunction "PE1_98") (pintype "bidirectional"))
    )
    (net (code "120") (name "unconnected-(U1-PE2-Pad1)") (class "Default")
      (node (ref "U1") (pin "1") (pinfunction "PE2_1") (pintype "bidirectional"))
    )
    (net (code "121") (name "unconnected-(U1-PE3-Pad2)") (class "Default")
      (node (ref "U1") (pin "2") (pinfunction "PE3_2") (pintype "bidirectional"))
    )
    (net (code "122") (name "unconnected-(U1-PE4-Pad3)") (class "Default")
      (node (ref "U1") (pin "3") (pinfunction "PE4_3") (pintype "bidirectional"))
    )
    (net (code "123") (name "unconnected-(U1-PE5-Pad4)") (class "Default")
      (node (ref "U1") (pin "4") (pinfunction "PE5_4") (pintype "bidirectional"))
    )
    (net (code "124") (name "unconnected-(U1-PE6-Pad5)") (class "Default")
      (node (ref "U1") (pin "5") (pinfunction "PE6_5") (pintype "bidirectional"))
    )
    (net (code "125") (name "unconnected-(U1-PE7-Pad38)") (class "Default")
      (node (ref "U1") (pin "38") (pinfunction "PE7_38") (pintype "bidirectional"))
    )
    (net (code "126") (name "unconnected-(U1-PE8-Pad39)") (class "Default")
      (node (ref "U1") (pin "39") (pinfunction "PE8_39") (pintype "bidirectional"))
    )
    (net (code "127") (name "unconnected-(U1-PE9-Pad40)") (class "Default")
      (node (ref "U1") (pin "40") (pinfunction "PE9_40") (pintype "bidirectional"))
    )
    (net (code "128") (name "unconnected-(U1-PE10-Pad41)") (class "Default")
      (node (ref "U1") (pin "41") (pinfunction "PE10_41") (pintype "bidirectional"))
    )
    (net (code "129") (name "unconnected-(U1-PE11-Pad42)") (class "Default")
      (node (ref "U1") (pin "42") (pinfunction "PE11_42") (pintype "bidirectional"))
    )
    (net (code "130") (name "unconnected-(U1-VBAT-Pad6)") (class "Default")
      (node (ref "U1") (pin "6") (pinfunction "VBAT_6") (pintype "power_in"))
    )
    (net (code "131") (name "unconnected-(U1-VREF+-Pad21)") (class "Default")
      (node (ref "U1") (pin "21") (pinfunction "VREF+_21") (pintype "power_in"))
    )
    (net (code "132") (name "unconnected-(U1-VREF--Pad20)") (class "Default")
      (node (ref "U1") (pin "20") (pinfunction "VREF-_20") (pintype "power_in"))
    )
    (net (code "133") (name "unconnected-(U2-D1-Pad25)") (class "Default")
      (node (ref "U2") (pin "25") (pinfunction "D1_25") (pintype "passive"))
    )
    (net (code "134") (name "unconnected-(U2-D2-Pad26)") (class "Default")
      (node (ref "U2") (pin "26") (pinfunction "D2_26") (pintype "passive"))
    )
    (net (code "135") (name "unconnected-(U2-D3-Pad27)") (class "Default")
      (node (ref "U2") (pin "27") (pinfunction "D3_27") (pintype "passive"))
    )
    (net (code "136") (name "unconnected-(U2-D4-Pad28)") (class "Default")
      (node (ref "U2") (pin "28") (pinfunction "D4_28") (pintype "passive"))
    )
    (net (code "137") (name "unconnected-(U2-SVDD-Pad9)") (class "Default")
      (node (ref "U2") (pin "9") (pinfunction "SVDD_9") (pintype "passive"))
    )
    (net (code "138") (name "unconnected-(U3-AUX1-Pad26)") (class "Default")
      (node (ref "U3") (pin "26") (pinfunction "AUX1_26") (pintype "passive"))
    )
    (net (code "139") (name "unconnected-(U3-AUX1UC-Pad31)") (class "Default")
      (node (ref "U3") (pin "31") (pinfunction "AUX1UC_31") (pintype "passive"))
    )
    (net (code "140") (name "unconnected-(U3-AUX2-Pad27)") (class "Default")
      (node (ref "U3") (pin "27") (pinfunction "AUX2_27") (pintype "passive"))
    )
    (net (code "141") (name "unconnected-(U3-AUX2UC-Pad32)") (class "Default")
      (node (ref "U3") (pin "32") (pinfunction "AUX2UC_32") (pintype "passive"))
    )
    (net (code "142") (name "unconnected-(U3-XTAL2-Pad13)") (class "Default")
      (node (ref "U3") (pin "13") (pinfunction "XTAL2_13") (pintype "passive"))
    )
  )
)
